# mainSchem.net
KiCad netlist of a schematic drawn in Altium Designer
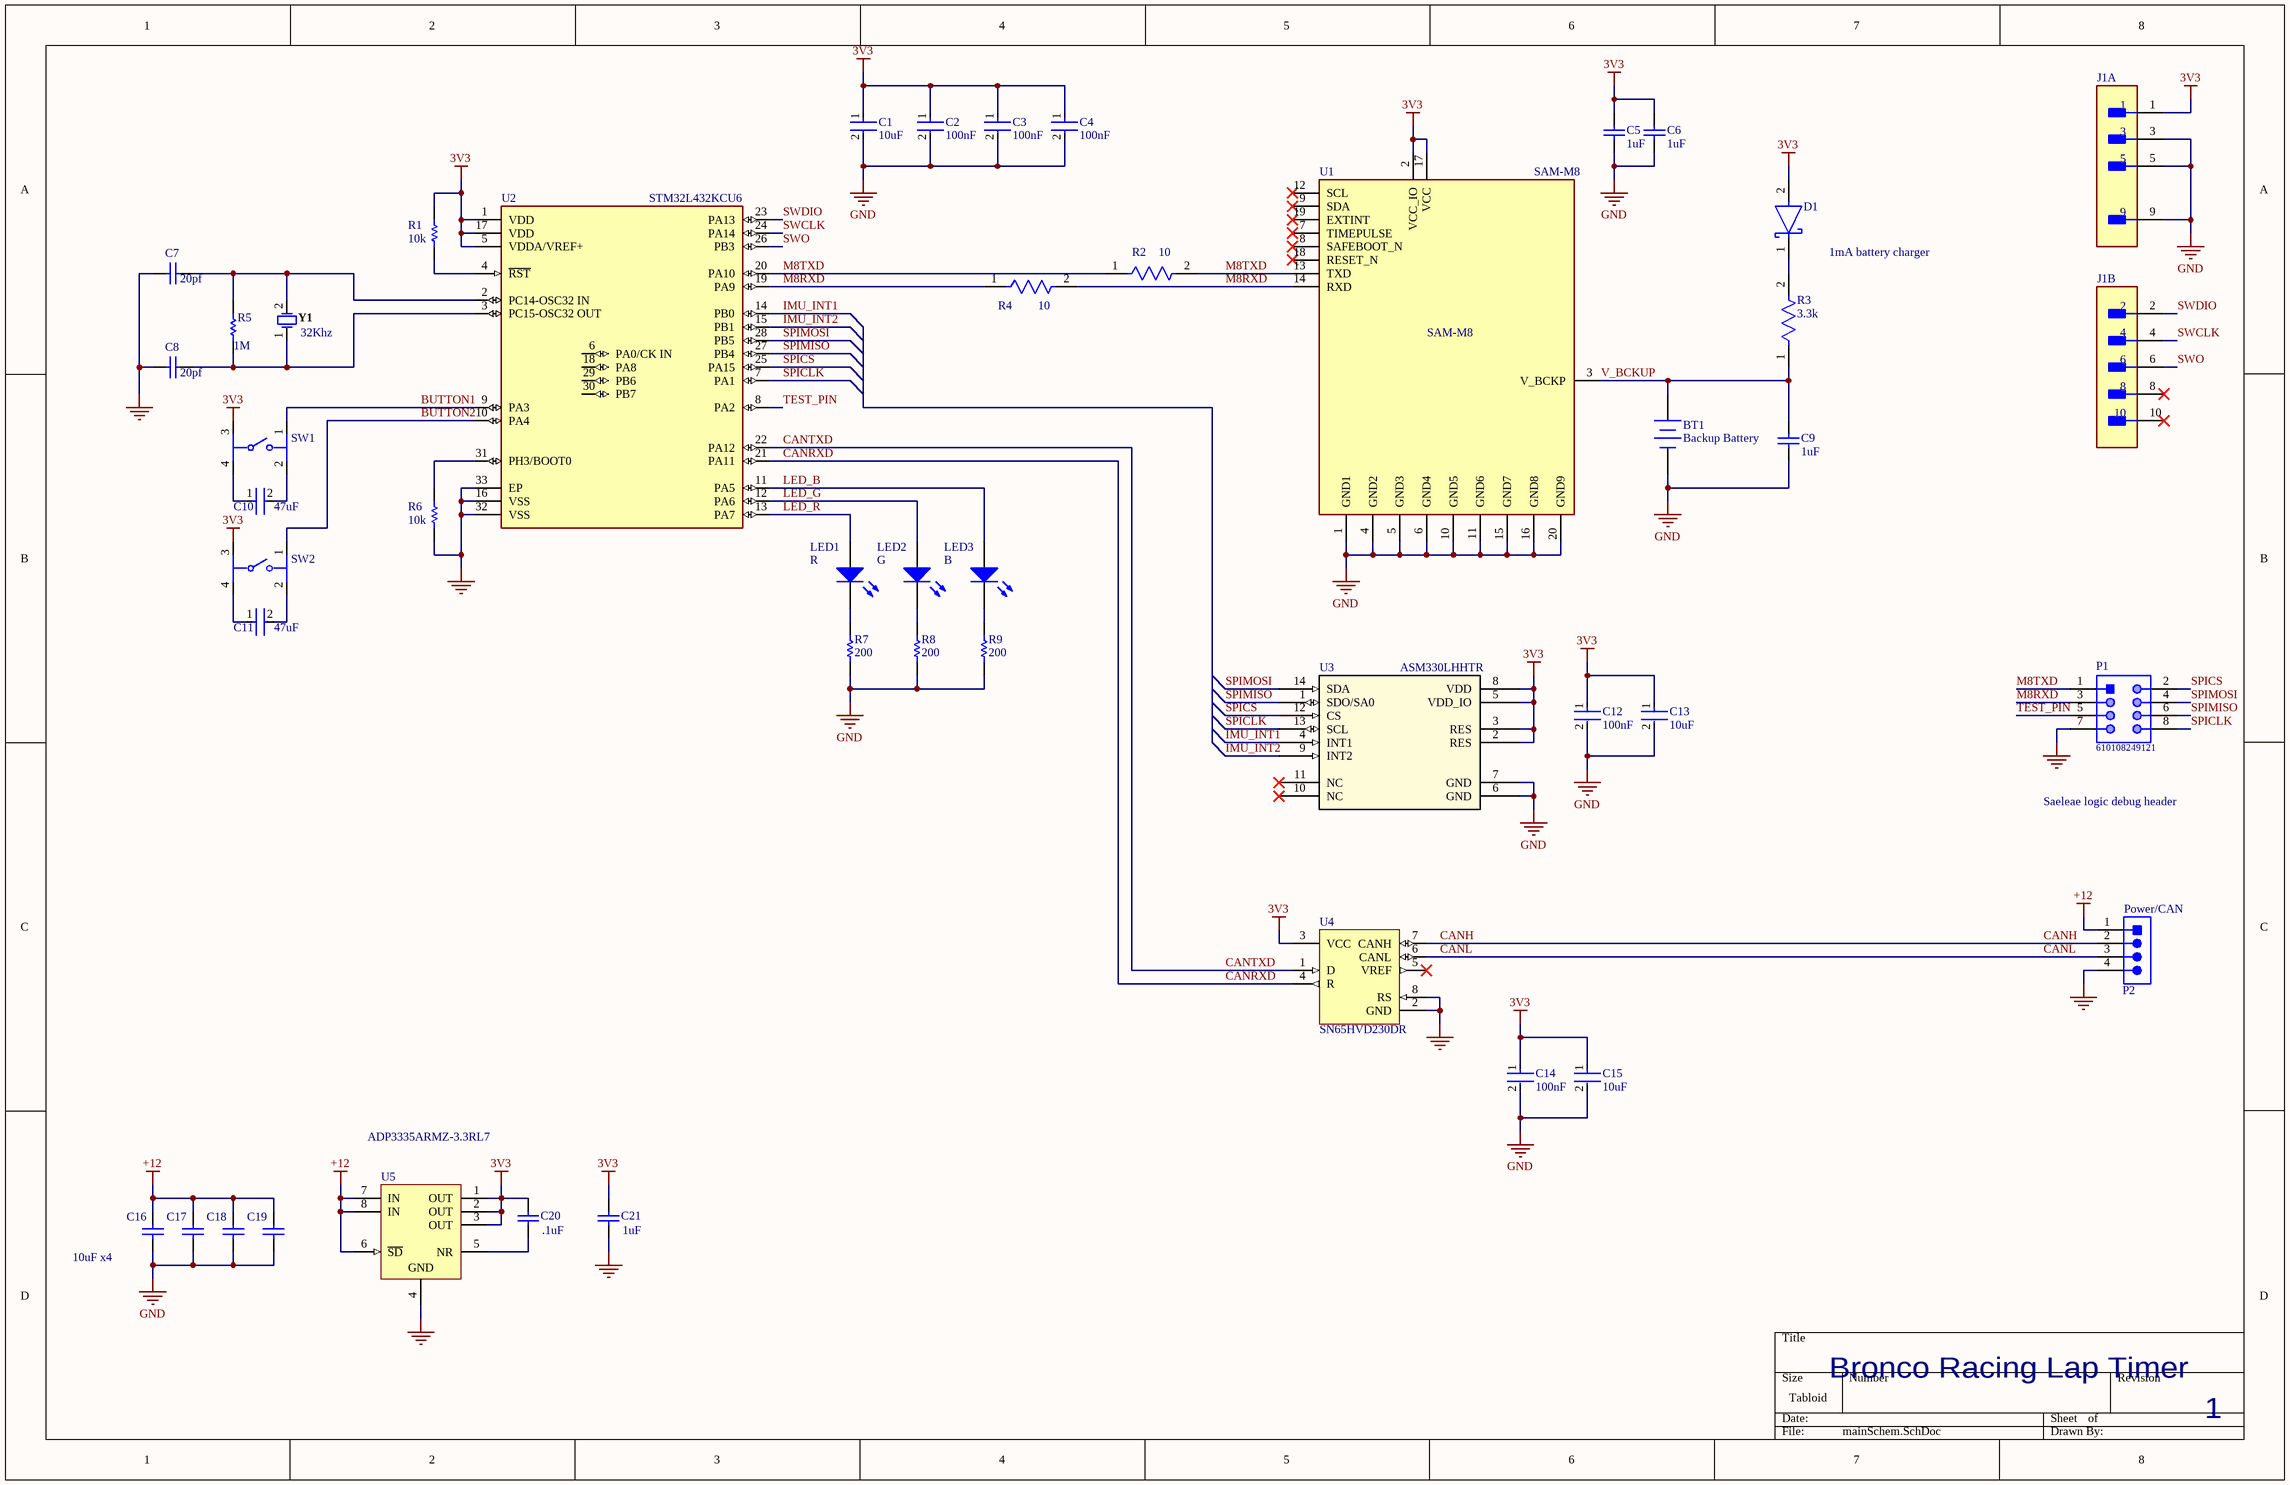
[diagram p0: mainSchem.SchDoc]

(export (version "E")
  (design (tool "Eeschema 10.0.6"))
  (components
    (comp (ref "BT1")
      (value "Backup Battery")
      (footprint "SEIK-MS621FE-FL11E-2_V")
      (description "MS Lihium Rechargeable Battery, 3 V, -20 to 60 degC, Tray")
      (fields (field (name "MANUFACTURER") "SeikoInstruments"))
      (libsource (lib "Altium Content Vault") (part "BATTERY_SINGLE-2"))
    )
    (comp (ref "C1")
      (value "10uF")
      (footprint "FP-C1608-080-MFG")
      (description "CAP CER 10UF 10V X5R 0603")
      (fields
        (field (name "MANUFACTURER PART NUMBER") "C1608X5R1A106K080AC")
        (field (name "OCTOPART") "https://octopart.com/c1608x5r1a106k080ac-tdk-26013468")
      )
      (libsource (lib "Altium Content Vault") (part "11868f565c42a9108669ba33697ecf6"))
    )
    (comp (ref "C2")
      (value "100nF")
      (footprint "FP-CGA3E-0_3-0_1-IPC_A")
      (description "Cap Ceramic 100nF 50V X7R 10% Pad SMD 0603 +125°C Automotive T/R")
      (fields (field (name "TOLERANCE") "10%") (field (name "VOLTAGE") "50V"))
      (libsource (lib "Altium Content Vault") (part "b4654b650e69147ec39a6b967a45e02"))
    )
    (comp (ref "C3")
      (value "100nF")
      (footprint "FP-CGA3E-0_3-0_1-IPC_A")
      (description "Cap Ceramic 100nF 50V X7R 10% Pad SMD 0603 +125°C Automotive T/R")
      (fields (field (name "TOLERANCE") "10%") (field (name "VOLTAGE") "50V"))
      (libsource (lib "Altium Content Vault") (part "b4654b650e69147ec39a6b967a45e02"))
    )
    (comp (ref "C4")
      (value "100nF")
      (footprint "FP-CGA3E-0_3-0_1-IPC_A")
      (description "Cap Ceramic 100nF 50V X7R 10% Pad SMD 0603 +125°C Automotive T/R")
      (fields (field (name "TOLERANCE") "10%") (field (name "VOLTAGE") "50V"))
      (libsource (lib "Altium Content Vault") (part "b4654b650e69147ec39a6b967a45e02"))
    )
    (comp (ref "C5")
      (value "1uF")
      (footprint "CAPC1608X90X35LL15T15")
      (fields (field (name "MANUFACTURER") "Kemet") (field (name "PART NUMBER") "C0603C105K3PAC7867"))
      (libsource (lib "Altium Content Vault") (part "CAP"))
    )
    (comp (ref "C6")
      (value "1uF")
      (footprint "CAPC1608X90X35LL15T15")
      (fields (field (name "MANUFACTURER") "Kemet") (field (name "PART NUMBER") "C0603C105K3PAC7867"))
      (libsource (lib "Altium Content Vault") (part "CAP"))
    )
    (comp (ref "C7")
      (value "08051A200JAT2A")
      (footprint "CAPC2013X140X50NL20T25")
      (fields (field (name "MANUFACTURER") "AVX Interconnect / Elco"))
      (libsource (lib "Altium Content Vault") (part "CAP"))
    )
    (comp (ref "C8")
      (value "08051A200JAT2A")
      (footprint "CAPC2013X140X50NL20T25")
      (fields (field (name "MANUFACTURER") "AVX Interconnect / Elco"))
      (libsource (lib "Altium Content Vault") (part "CAP"))
    )
    (comp (ref "C9")
      (value "1uF")
      (footprint "CAPC1608X90X35LL15T15")
      (fields (field (name "MANUFACTURER") "Kemet") (field (name "PART NUMBER") "C0603C105K3PAC7867"))
      (libsource (lib "Altium Content Vault") (part "CAP"))
    )
    (comp (ref "C10")
      (value "47uF")
      (footprint "FP-GRM188-0_2-IPC_B")
      (description "Chip Multilayer Ceramic Capacitors for General Purpose, 0603, 47uF, X5R, 15%, 20%, 6.3V")
      (fields (field (name "TOLERANCE") "20%"))
      (libsource (lib "Altium Content Vault") (part "11868f565c42a9108669ba33697ecf6"))
    )
    (comp (ref "C11")
      (value "47uF")
      (footprint "FP-GRM188-0_2-IPC_B")
      (description "Chip Multilayer Ceramic Capacitors for General Purpose, 0603, 47uF, X5R, 15%, 20%, 6.3V")
      (fields (field (name "TOLERANCE") "20%"))
      (libsource (lib "Altium Content Vault") (part "11868f565c42a9108669ba33697ecf6"))
    )
    (comp (ref "C12")
      (value "100nF")
      (footprint "FP-CGA3E-0_3-0_1-IPC_A")
      (description "Cap Ceramic 100nF 50V X7R 10% Pad SMD 0603 +125°C Automotive T/R")
      (fields (field (name "TOLERANCE") "10%") (field (name "VOLTAGE") "50V"))
      (libsource (lib "Altium Content Vault") (part "b4654b650e69147ec39a6b967a45e02"))
    )
    (comp (ref "C13")
      (value "10uF")
      (footprint "FP-C1608-080-MFG")
      (description "CAP CER 10UF 10V X5R 0603")
      (fields
        (field (name "MANUFACTURER PART NUMBER") "C1608X5R1A106K080AC")
        (field (name "OCTOPART") "https://octopart.com/c1608x5r1a106k080ac-tdk-26013468")
      )
      (libsource (lib "Altium Content Vault") (part "11868f565c42a9108669ba33697ecf6"))
    )
    (comp (ref "C14")
      (value "100nF")
      (footprint "FP-CGA3E-0_3-0_1-IPC_A")
      (description "Cap Ceramic 100nF 50V X7R 10% Pad SMD 0603 +125°C Automotive T/R")
      (fields (field (name "TOLERANCE") "10%") (field (name "VOLTAGE") "50V"))
      (libsource (lib "Altium Content Vault") (part "b4654b650e69147ec39a6b967a45e02"))
    )
    (comp (ref "C15")
      (value "10uF")
      (footprint "FP-C1608-080-MFG")
      (description "CAP CER 10UF 10V X5R 0603")
      (fields
        (field (name "MANUFACTURER PART NUMBER") "C1608X5R1A106K080AC")
        (field (name "OCTOPART") "https://octopart.com/c1608x5r1a106k080ac-tdk-26013468")
      )
      (libsource (lib "Altium Content Vault") (part "11868f565c42a9108669ba33697ecf6"))
    )
    (comp (ref "C16")
      (value "CGA5L3X5R1H106K160AB")
      (footprint "CAPC3216X190X20LL20")
      (description "Chip Capacitor, 10 uF, +/- 10%, 50 V, -55 to 85 degC, 1206 (3216 Metric), RoHS, Tape and Reel")
      (fields (field (name "MANUFACTURER") "TDK") (field (name "TOLERANCE") "10%"))
      (libsource (lib "Altium Content Vault") (part "CAP-NP-2"))
    )
    (comp (ref "C17")
      (value "CGA5L3X5R1H106K160AB")
      (footprint "CAPC3216X190X20LL20")
      (description "Chip Capacitor, 10 uF, +/- 10%, 50 V, -55 to 85 degC, 1206 (3216 Metric), RoHS, Tape and Reel")
      (fields (field (name "MANUFACTURER") "TDK") (field (name "TOLERANCE") "10%"))
      (libsource (lib "Altium Content Vault") (part "CAP-NP-2"))
    )
    (comp (ref "C18")
      (value "CGA5L3X5R1H106K160AB")
      (footprint "CAPC3216X190X20LL20")
      (description "Chip Capacitor, 10 uF, +/- 10%, 50 V, -55 to 85 degC, 1206 (3216 Metric), RoHS, Tape and Reel")
      (fields (field (name "MANUFACTURER") "TDK") (field (name "TOLERANCE") "10%"))
      (libsource (lib "Altium Content Vault") (part "CAP-NP-2"))
    )
    (comp (ref "C19")
      (value "CGA5L3X5R1H106K160AB")
      (footprint "CAPC3216X190X20LL20")
      (description "Chip Capacitor, 10 uF, +/- 10%, 50 V, -55 to 85 degC, 1206 (3216 Metric), RoHS, Tape and Reel")
      (fields (field (name "MANUFACTURER") "TDK") (field (name "TOLERANCE") "10%"))
      (libsource (lib "Altium Content Vault") (part "CAP-NP-2"))
    )
    (comp (ref "C20")
      (value "CGA3E2X7R1H104K080AA")
      (footprint "CAPC1608X90X20LL10")
      (description "Chip Capacitor, 0.1 uF, +/- 10%, 50 V, -55 to 125 degC, 0603 (1608 Metric), RoHS, Tape and Reel")
      (fields (field (name "VOLTAGE") "50V") (field (name "TOLERANCE") "10%"))
      (libsource (lib "Altium Content Vault") (part "CAP-NP-2"))
    )
    (comp (ref "C21")
      (value "GRM31MR71H105KA88L")
      (footprint "CAPC3216X125X55LL15T25")
      (description "Chip Capacitor, 1 uF, +/- 10%, 50 V, -55 to 125 degC, 1206 (3216 Metric), RoHS, Tape and Reel")
      (fields (field (name "TOLERANCE") "10%") (field (name "MANUFACTURER") "Murata"))
      (libsource (lib "Altium Content Vault") (part "CAP-NP-2"))
    )
    (comp (ref "D1")
      (value "SD0603S040S0R2")
      (footprint "FP-SD0603-MFG")
      (description "DIODE SCHOTTKY 40V 200MA 0603")
      (fields
        (field (name "MANUFACTURER") "AVX")
        (field (name "OCTOPART") "https://octopart.com/sd0603s040s0r2-avx-24931763")
      )
      (libsource (lib "Altium Content Vault") (part "1d6ec82d83fb6aee721767c19dac4b9"))
    )
    (comp (ref "J1")
      (value "FTSH-105-01-L-DV-007-K")
      (footprint "FP-FTSH-105-01-L-DV-007-K-MFG")
      (description "CONN HEADER SMD 10POS 1.27MM")
      (fields
        (field (name "OCTOPART") "https://octopart.com/ftsh-105-01-l-dv-007-k-samtec-53647300")
        (field (name "MANUFACTURER") "Samtec")
      )
      (libsource (lib "Altium Content Vault") (part "7c368be3265735b2816d0cab4417f87"))
    )
    (comp (ref "LED1")
      (value "150120RS75000")
      (footprint "1206_A")
      (description "SMD mono-color Chip LED, WL-SMCW, Red")
      (fields (field (name "MANUFACTURER") "Wuerth Elektronik"))
      (libsource (lib "Altium Content Vault") (part "WE-LED_K1A2-2"))
    )
    (comp (ref "LED2")
      (value "150120GS75000")
      (footprint "1206_A")
      (description "SMD mono-color Chip LED, WL-SMCW, Green")
      (fields (field (name "MANUFACTURER") "Wuerth Elektronik"))
      (libsource (lib "Altium Content Vault") (part "WE-LED_K1A2-2"))
    )
    (comp (ref "LED3")
      (value "150120BS75000")
      (footprint "1206_A")
      (description "SMD mono-color Chip LED, WL-SMCW, Blue")
      (fields (field (name "MANUFACTURER") "Wuerth Elektronik"))
      (libsource (lib "Altium Content Vault") (part "WE-LED_K1A2-2"))
    )
    (comp (ref "P1")
      (value "610108249121")
      (footprint "610108249121")
      (description "SMT Angled Pin Header WR-PHD, Pitch 2.54 mm, Dual Row, 8 pins")
      (fields (field (name "MANUFACTURER") "Wurth Elektronik") (field (name "PUBLISHER") "WurthElektronik"))
      (libsource (lib "Altium Content Vault") (part "WE-CN-2P-M-R8"))
    )
    (comp (ref "P2")
      (value "B4B-PH-K-S(LF)(SN)")
      (footprint "JST-B4B-PH-K-S_V")
      (fields (field (name "MANUFACTURER") "JST"))
      (libsource (lib "Altium Content Vault") (part "CN-1P-M-R4"))
    )
    (comp (ref "R1")
      (value "10k")
      (footprint "RESC1609X55X30LL15T15")
      (description "Chip Resistor, 10 KOhm, +/- 1%, 0.1 W, -55 to 155 degC, 0603 (1608 Metric), RoHS, Tape and Reel")
      (fields (field (name "TOLERANCE") "1%") (field (name "MANUFACTURER") "Panasonic"))
      (libsource (lib "Altium Content Vault") (part "RES-2"))
    )
    (comp (ref "R2")
      (value "10")
      (footprint "FP-RT0603-MFG")
      (description "RES SMD 10 OHM 0.1% 1/10W 0603")
      (fields (field (name "TOLERANCE") "0.001") (field (name "MANUFACTURER") "Yageo"))
      (libsource (lib "Altium Content Vault") (part "1029c3af85768c4190bb7ad29bc67b5"))
    )
    (comp (ref "R3")
      (value "3.3k")
      (footprint "FP-RT0603-MFG")
      (description "RES 3.30K OHM 1/10W 1% SMD 0603")
      (fields
        (field (name "OCTOPART") "https://octopart.com/rt0603fre073k3l-yageo-39814754")
        (field (name "MANUFACTURER PART NUMBER") "RT0603FRE073K3L")
      )
      (libsource (lib "Altium Content Vault") (part "1029c3af85768c4190bb7ad29bc67b5"))
    )
    (comp (ref "R4")
      (value "10")
      (footprint "FP-RT0603-MFG")
      (description "RES SMD 10 OHM 0.1% 1/10W 0603")
      (fields (field (name "TOLERANCE") "0.001") (field (name "MANUFACTURER") "Yageo"))
      (libsource (lib "Altium Content Vault") (part "1029c3af85768c4190bb7ad29bc67b5"))
    )
    (comp (ref "R5")
      (value "ERJ-8ENF1004V")
      (footprint "RESC3216X70X50NL05T20")
      (fields (field (name "MANUFACTURER") "Panasonic"))
      (libsource (lib "Altium Content Vault") (part "RES"))
    )
    (comp (ref "R6")
      (value "10k")
      (footprint "RESC1609X55X30LL15T15")
      (description "Chip Resistor, 10 KOhm, +/- 1%, 0.1 W, -55 to 155 degC, 0603 (1608 Metric), RoHS, Tape and Reel")
      (fields (field (name "TOLERANCE") "1%") (field (name "MANUFACTURER") "Panasonic"))
      (libsource (lib "Altium Content Vault") (part "RES-2"))
    )
    (comp (ref "R7")
      (value "200")
      (footprint "RESC1609X55X30NL10T20")
      (fields (field (name "PART NUMBER") "TNPW0603200RBEEA") (field (name "MANUFACTURER") "Vishay Dale"))
      (libsource (lib "Altium Content Vault") (part "RES"))
    )
    (comp (ref "R8")
      (value "200")
      (footprint "RESC1609X55X30NL10T20")
      (fields (field (name "PART NUMBER") "TNPW0603200RBEEA") (field (name "MANUFACTURER") "Vishay Dale"))
      (libsource (lib "Altium Content Vault") (part "RES"))
    )
    (comp (ref "R9")
      (value "200")
      (footprint "RESC1609X55X30NL10T20")
      (fields (field (name "PART NUMBER") "TNPW0603200RBEEA") (field (name "MANUFACTURER") "Vishay Dale"))
      (libsource (lib "Altium Content Vault") (part "RES"))
    )
    (comp (ref "SW1")
      (value "PTS645SM43SMTR92LFS")
      (footprint "FP-PTS645SM43SMTR92LFS-MFG")
      (description "SWITCH TACTILE SPST-NO 0.05A 12V")
      (libsource (lib "Altium Content Vault") (part "1adf0dd01260c80cf25a44bfd6b99ba"))
    )
    (comp (ref "SW2")
      (value "PTS645SM43SMTR92LFS")
      (footprint "FP-PTS645SM43SMTR92LFS-MFG")
      (description "SWITCH TACTILE SPST-NO 0.05A 12V")
      (libsource (lib "Altium Content Vault") (part "1adf0dd01260c80cf25a44bfd6b99ba"))
    )
    (comp (ref "U1")
      (value "SAM-M8")
      (footprint "SAM-M8")
      (description "u-blox SAM GNSS antenna module")
      (fields (field (name "MANUFACTURER") "u-blox"))
      (libsource (lib "ubloxLib") (part "SAM-M8"))
    )
    (comp (ref "U2")
      (value "STM32L432KCU6")
      (footprint "FP-UFQFPN32-A0B8-MFG")
      (description "IC MCU 32BIT 256KB FLASH 32QFPN")
      (fields
        (field (name "OCTOPART") "https://octopart.com/stm32l432kcu6-stmicroelectronics-71093510")
        (field (name "MANUFACTURER") "STMicroelectronics")
      )
      (libsource (lib "Altium Content Vault") (part "f3240dca552e0aa49c1b4baba198c12"))
    )
    (comp (ref "U3")
      (value "ASM330LHHTR")
      (footprint "LGA-14L_2P5X3X0P83_STM")
      (description "No Description Available")
      (fields (field (name "COPYRIGHT") "Copyright (C) 2018 Accelerated Designs. All rights reserved"))
      (libsource (lib "2021-01-05_19-36-17") (part "ASM330LHHTR"))
    )
    (comp (ref "U4")
      (value "SN65HVD230DR")
      (footprint "D0008A_L")
      (fields (field (name "MANUFACTURER") "Texas Instruments"))
      (libsource (lib "Altium Content Vault") (part "TI-SN65HVD230-SOIC_D-8"))
    )
    (comp (ref "U5")
      (value "ADP3335ARMZ-3.3RL7")
      (footprint "ADI-RM-8_L")
      (fields (field (name "MANUFACTURER") "Analog Devices"))
      (libsource (lib "Altium Content Vault") (part "ADI-ADP3335-RM-8"))
    )
    (comp (ref "Y1")
      (value "ABS07-120-32.768KHZ-T")
      (footprint "ABRA-ABS07_A_V")
      (description "Tuning Fork Crystal, 32.768 KHz, +/- 20 ppm, -40 to 85 degC, 2-Pin SMD, RoHS, Tape and Reel")
      (fields (field (name "MANUFACTURER") "Abracon") (field (name "TOLERANCE") "20ppm"))
      (libsource (lib "Altium Content Vault") (part "XTAL-1-2-2"))
    )
  )
  (nets
    (net (code "1") (name "+12") (class "Default")
      (node (ref "C16") (pin "1") (pinfunction "1_1") (pintype "passive"))
      (node (ref "C17") (pin "1") (pinfunction "1_1") (pintype "passive"))
      (node (ref "C18") (pin "1") (pinfunction "1_1") (pintype "passive"))
      (node (ref "C19") (pin "1") (pinfunction "1_1") (pintype "passive"))
      (node (ref "P2") (pin "1") (pinfunction "1_1") (pintype "passive"))
      (node (ref "U5") (pin "6") (pinfunction "~{SD}_6") (pintype "input"))
      (node (ref "U5") (pin "7") (pinfunction "IN_7") (pintype "power_in"))
      (node (ref "U5") (pin "8") (pinfunction "IN_8") (pintype "power_in"))
    )
    (net (code "3") (name "/BUTTON1") (class "Default")
      (node (ref "SW1") (pin "1") (pinfunction "1_1") (pintype "passive"))
      (node (ref "U2") (pin "9") (pinfunction "PA3_9") (pintype "bidirectional"))
    )
    (net (code "4") (name "/BUTTON2") (class "Default")
      (node (ref "SW2") (pin "1") (pinfunction "1_1") (pintype "passive"))
      (node (ref "U2") (pin "10") (pinfunction "PA4_10") (pintype "bidirectional"))
    )
    (net (code "5") (name "/CANH") (class "Default")
      (node (ref "P2") (pin "2") (pinfunction "2_2") (pintype "passive"))
      (node (ref "U4") (pin "7") (pinfunction "CANH_7") (pintype "bidirectional"))
    )
    (net (code "6") (name "/CANL") (class "Default")
      (node (ref "P2") (pin "3") (pinfunction "3_3") (pintype "passive"))
      (node (ref "U4") (pin "6") (pinfunction "CANL_6") (pintype "bidirectional"))
    )
    (net (code "7") (name "/CANRXD") (class "Default")
      (node (ref "U2") (pin "21") (pinfunction "PA11_21") (pintype "bidirectional"))
      (node (ref "U4") (pin "4") (pinfunction "R_4") (pintype "output"))
    )
    (net (code "8") (name "/CANTXD") (class "Default")
      (node (ref "U2") (pin "22") (pinfunction "PA12_22") (pintype "bidirectional"))
      (node (ref "U4") (pin "1") (pinfunction "D_1") (pintype "input"))
    )
    (net (code "9") (name "/IMU_INT1") (class "Default")
      (node (ref "U2") (pin "14") (pinfunction "PB0_14") (pintype "bidirectional"))
      (node (ref "U3") (pin "4") (pinfunction "INT1_4") (pintype "input"))
    )
    (net (code "10") (name "/IMU_INT2") (class "Default")
      (node (ref "U2") (pin "15") (pinfunction "PB1_15") (pintype "bidirectional"))
      (node (ref "U3") (pin "9") (pinfunction "INT2_9") (pintype "input"))
    )
    (net (code "11") (name "/LED_B") (class "Default")
      (node (ref "LED3") (pin "2") (pinfunction "A_2") (pintype "passive"))
      (node (ref "U2") (pin "11") (pinfunction "PA5_11") (pintype "bidirectional"))
    )
    (net (code "12") (name "/LED_G") (class "Default")
      (node (ref "LED2") (pin "2") (pinfunction "A_2") (pintype "passive"))
      (node (ref "U2") (pin "12") (pinfunction "PA6_12") (pintype "bidirectional"))
    )
    (net (code "13") (name "/LED_R") (class "Default")
      (node (ref "LED1") (pin "2") (pinfunction "A_2") (pintype "passive"))
      (node (ref "U2") (pin "13") (pinfunction "PA7_13") (pintype "bidirectional"))
    )
    (net (code "14") (name "/M8RXD") (class "Default")
      (node (ref "P1") (pin "3") (pinfunction "3_3") (pintype "passive"))
      (node (ref "R4") (pin "1") (pinfunction "1_1") (pintype "passive"))
      (node (ref "R4") (pin "2") (pinfunction "2_2") (pintype "passive"))
      (node (ref "U1") (pin "14") (pinfunction "RXD_14") (pintype "passive"))
      (node (ref "U2") (pin "19") (pinfunction "PA9_19") (pintype "bidirectional"))
    )
    (net (code "15") (name "/M8TXD") (class "Default")
      (node (ref "P1") (pin "1") (pinfunction "1_1") (pintype "passive"))
      (node (ref "R2") (pin "1") (pinfunction "1_1") (pintype "passive"))
      (node (ref "R2") (pin "2") (pinfunction "2_2") (pintype "passive"))
      (node (ref "U1") (pin "13") (pinfunction "TXD_13") (pintype "passive"))
      (node (ref "U2") (pin "20") (pinfunction "PA10_20") (pintype "bidirectional"))
    )
    (net (code "16") (name "/SPICLK") (class "Default")
      (node (ref "P1") (pin "8") (pinfunction "8_8") (pintype "passive"))
      (node (ref "U2") (pin "7") (pinfunction "PA1_7") (pintype "bidirectional"))
      (node (ref "U3") (pin "13") (pinfunction "SCL_13") (pintype "bidirectional"))
    )
    (net (code "17") (name "/SPICS") (class "Default")
      (node (ref "P1") (pin "2") (pinfunction "2_2") (pintype "passive"))
      (node (ref "U2") (pin "25") (pinfunction "PA15_25") (pintype "bidirectional"))
      (node (ref "U3") (pin "12") (pinfunction "CS_12") (pintype "input"))
    )
    (net (code "18") (name "/SPIMISO") (class "Default")
      (node (ref "P1") (pin "6") (pinfunction "6_6") (pintype "passive"))
      (node (ref "U2") (pin "27") (pinfunction "PB4_27") (pintype "bidirectional"))
      (node (ref "U3") (pin "1") (pinfunction "SDO/SA0_1") (pintype "bidirectional"))
    )
    (net (code "19") (name "/SPIMOSI") (class "Default")
      (node (ref "P1") (pin "4") (pinfunction "4_4") (pintype "passive"))
      (node (ref "U2") (pin "28") (pinfunction "PB5_28") (pintype "bidirectional"))
      (node (ref "U3") (pin "14") (pinfunction "SDA_14") (pintype "input"))
    )
    (net (code "20") (name "/SWCLK") (class "Default")
      (node (ref "J1") (pin "4") (pinfunction "4_4") (pintype "passive"))
      (node (ref "U2") (pin "24") (pinfunction "PA14_24") (pintype "bidirectional"))
    )
    (net (code "21") (name "/SWDIO") (class "Default")
      (node (ref "J1") (pin "2") (pinfunction "2_2") (pintype "passive"))
      (node (ref "U2") (pin "23") (pinfunction "PA13_23") (pintype "bidirectional"))
    )
    (net (code "22") (name "/SWO") (class "Default")
      (node (ref "J1") (pin "6") (pinfunction "6_6") (pintype "passive"))
      (node (ref "U2") (pin "26") (pinfunction "PB3_26") (pintype "bidirectional"))
    )
    (net (code "23") (name "/TEST_PIN") (class "Default")
      (node (ref "P1") (pin "5") (pinfunction "5_5") (pintype "passive"))
      (node (ref "U2") (pin "8") (pinfunction "PA2_8") (pintype "bidirectional"))
    )
    (net (code "24") (name "/V_BCKUP") (class "Default")
      (node (ref "BT1") (pin "1") (pinfunction "+_1") (pintype "passive"))
      (node (ref "C9") (pin "2") (pinfunction "2_2") (pintype "passive"))
      (node (ref "R3") (pin "1") (pinfunction "1_1") (pintype "passive"))
      (node (ref "U1") (pin "3") (pinfunction "V_BCKP_3") (pintype "passive"))
    )
    (net (code "25") (name "3V3") (class "Default")
      (node (ref "C1") (pin "1") (pinfunction "1_1") (pintype "passive"))
      (node (ref "C12") (pin "1") (pinfunction "1_1") (pintype "passive"))
      (node (ref "C13") (pin "1") (pinfunction "1_1") (pintype "passive"))
      (node (ref "C14") (pin "1") (pinfunction "1_1") (pintype "passive"))
      (node (ref "C15") (pin "1") (pinfunction "1_1") (pintype "passive"))
      (node (ref "C2") (pin "1") (pinfunction "1_1") (pintype "passive"))
      (node (ref "C20") (pin "1") (pinfunction "1_1") (pintype "passive"))
      (node (ref "C21") (pin "1") (pinfunction "1_1") (pintype "passive"))
      (node (ref "C3") (pin "1") (pinfunction "1_1") (pintype "passive"))
      (node (ref "C4") (pin "1") (pinfunction "1_1") (pintype "passive"))
      (node (ref "C5") (pin "2") (pinfunction "2_2") (pintype "passive"))
      (node (ref "C6") (pin "2") (pinfunction "2_2") (pintype "passive"))
      (node (ref "D1") (pin "2") (pinfunction "A_2") (pintype "passive"))
      (node (ref "J1") (pin "1") (pinfunction "1_1") (pintype "passive"))
      (node (ref "R1") (pin "1") (pinfunction "1_1") (pintype "passive"))
      (node (ref "SW1") (pin "3") (pinfunction "3_3") (pintype "passive"))
      (node (ref "SW2") (pin "3") (pinfunction "3_3") (pintype "passive"))
      (node (ref "U1") (pin "17") (pinfunction "VCC_17") (pintype "passive"))
      (node (ref "U1") (pin "2") (pinfunction "VCC_IO_2") (pintype "passive"))
      (node (ref "U2") (pin "1") (pinfunction "VDD_1") (pintype "power_in"))
      (node (ref "U2") (pin "17") (pinfunction "VDD_17") (pintype "power_in"))
      (node (ref "U2") (pin "5") (pinfunction "VDDA/VREF+_5") (pintype "power_in"))
      (node (ref "U3") (pin "2") (pinfunction "RES_2") (pintype "passive"))
      (node (ref "U3") (pin "3") (pinfunction "RES_3") (pintype "passive"))
      (node (ref "U3") (pin "5") (pinfunction "VDD_IO_5") (pintype "power_in"))
      (node (ref "U3") (pin "8") (pinfunction "VDD_8") (pintype "power_in"))
      (node (ref "U4") (pin "3") (pinfunction "VCC_3") (pintype "power_in"))
      (node (ref "U5") (pin "1") (pinfunction "OUT_1") (pintype "power_in"))
      (node (ref "U5") (pin "2") (pinfunction "OUT_2") (pintype "power_in"))
      (node (ref "U5") (pin "3") (pinfunction "OUT_3") (pintype "power_in"))
    )
    (net (code "26") (name "GND") (class "Default")
      (node (ref "BT1") (pin "2") (pinfunction "-_2") (pintype "passive"))
      (node (ref "C1") (pin "2") (pinfunction "2_2") (pintype "passive"))
      (node (ref "C12") (pin "2") (pinfunction "2_2") (pintype "passive"))
      (node (ref "C13") (pin "2") (pinfunction "2_2") (pintype "passive"))
      (node (ref "C14") (pin "2") (pinfunction "2_2") (pintype "passive"))
      (node (ref "C15") (pin "2") (pinfunction "2_2") (pintype "passive"))
      (node (ref "C16") (pin "2") (pinfunction "2_2") (pintype "passive"))
      (node (ref "C17") (pin "2") (pinfunction "2_2") (pintype "passive"))
      (node (ref "C18") (pin "2") (pinfunction "2_2") (pintype "passive"))
      (node (ref "C19") (pin "2") (pinfunction "2_2") (pintype "passive"))
      (node (ref "C2") (pin "2") (pinfunction "2_2") (pintype "passive"))
      (node (ref "C21") (pin "2") (pinfunction "2_2") (pintype "passive"))
      (node (ref "C3") (pin "2") (pinfunction "2_2") (pintype "passive"))
      (node (ref "C4") (pin "2") (pinfunction "2_2") (pintype "passive"))
      (node (ref "C5") (pin "1") (pinfunction "1_1") (pintype "passive"))
      (node (ref "C6") (pin "1") (pinfunction "1_1") (pintype "passive"))
      (node (ref "C7") (pin "1") (pinfunction "1_1") (pintype "passive"))
      (node (ref "C8") (pin "1") (pinfunction "1_1") (pintype "passive"))
      (node (ref "C9") (pin "1") (pinfunction "1_1") (pintype "passive"))
      (node (ref "J1") (pin "3") (pinfunction "3_3") (pintype "passive"))
      (node (ref "J1") (pin "5") (pinfunction "5_5") (pintype "passive"))
      (node (ref "J1") (pin "9") (pinfunction "9_9") (pintype "passive"))
      (node (ref "P1") (pin "7") (pinfunction "7_7") (pintype "passive"))
      (node (ref "P2") (pin "4") (pinfunction "4_4") (pintype "passive"))
      (node (ref "R6") (pin "2") (pinfunction "2_2") (pintype "passive"))
      (node (ref "R7") (pin "1") (pinfunction "1_1") (pintype "passive"))
      (node (ref "R8") (pin "1") (pinfunction "1_1") (pintype "passive"))
      (node (ref "R9") (pin "1") (pinfunction "1_1") (pintype "passive"))
      (node (ref "U1") (pin "1") (pinfunction "GND1_1") (pintype "passive"))
      (node (ref "U1") (pin "10") (pinfunction "GND5_10") (pintype "passive"))
      (node (ref "U1") (pin "11") (pinfunction "GND6_11") (pintype "passive"))
      (node (ref "U1") (pin "15") (pinfunction "GND7_15") (pintype "passive"))
      (node (ref "U1") (pin "16") (pinfunction "GND8_16") (pintype "passive"))
      (node (ref "U1") (pin "20") (pinfunction "GND9_20") (pintype "passive"))
      (node (ref "U1") (pin "4") (pinfunction "GND2_4") (pintype "passive"))
      (node (ref "U1") (pin "5") (pinfunction "GND3_5") (pintype "passive"))
      (node (ref "U1") (pin "6") (pinfunction "GND4_6") (pintype "passive"))
      (node (ref "U2") (pin "16") (pinfunction "VSS_16") (pintype "power_in"))
      (node (ref "U2") (pin "32") (pinfunction "VSS_32") (pintype "power_in"))
      (node (ref "U2") (pin "33") (pinfunction "EP_33") (pintype "power_in"))
      (node (ref "U3") (pin "6") (pinfunction "GND_6") (pintype "passive"))
      (node (ref "U3") (pin "7") (pinfunction "GND_7") (pintype "passive"))
      (node (ref "U4") (pin "2") (pinfunction "GND_2") (pintype "power_in"))
      (node (ref "U4") (pin "8") (pinfunction "RS_8") (pintype "input"))
      (node (ref "U5") (pin "4") (pinfunction "GND_4") (pintype "power_in"))
    )
    (net (code "27") (name "Net-(C10-Pad1)") (class "Default")
      (node (ref "C10") (pin "1") (pinfunction "1_1") (pintype "passive"))
      (node (ref "SW1") (pin "4") (pinfunction "4_4") (pintype "passive"))
    )
    (net (code "28") (name "Net-(C10-Pad2)") (class "Default")
      (node (ref "C10") (pin "2") (pinfunction "2_2") (pintype "passive"))
      (node (ref "SW1") (pin "2") (pinfunction "2_2") (pintype "passive"))
    )
    (net (code "29") (name "Net-(C11-Pad1)") (class "Default")
      (node (ref "C11") (pin "1") (pinfunction "1_1") (pintype "passive"))
      (node (ref "SW2") (pin "4") (pinfunction "4_4") (pintype "passive"))
    )
    (net (code "30") (name "Net-(C11-Pad2)") (class "Default")
      (node (ref "C11") (pin "2") (pinfunction "2_2") (pintype "passive"))
      (node (ref "SW2") (pin "2") (pinfunction "2_2") (pintype "passive"))
    )
    (net (code "31") (name "Net-(D1-C)") (class "Default")
      (node (ref "D1") (pin "1") (pinfunction "C_1") (pintype "passive"))
      (node (ref "R3") (pin "2") (pinfunction "2_2") (pintype "passive"))
    )
    (net (code "32") (name "Net-(LED1-K)") (class "Default")
      (node (ref "LED1") (pin "1") (pinfunction "K_1") (pintype "passive"))
      (node (ref "R7") (pin "2") (pinfunction "2_2") (pintype "passive"))
    )
    (net (code "33") (name "Net-(LED2-K)") (class "Default")
      (node (ref "LED2") (pin "1") (pinfunction "K_1") (pintype "passive"))
      (node (ref "R8") (pin "2") (pinfunction "2_2") (pintype "passive"))
    )
    (net (code "34") (name "Net-(LED3-K)") (class "Default")
      (node (ref "LED3") (pin "1") (pinfunction "K_1") (pintype "passive"))
      (node (ref "R9") (pin "2") (pinfunction "2_2") (pintype "passive"))
    )
    (net (code "35") (name "Net-(U2-PC14-OSC32_IN)") (class "Default")
      (node (ref "C7") (pin "2") (pinfunction "2_2") (pintype "passive"))
      (node (ref "R5") (pin "1") (pinfunction "1_1") (pintype "passive"))
      (node (ref "U2") (pin "2") (pinfunction "PC14-OSC32_IN_2") (pintype "bidirectional"))
      (node (ref "Y1") (pin "2") (pinfunction "2_2") (pintype "passive"))
    )
    (net (code "36") (name "Net-(U2-PC15-OSC32_OUT)") (class "Default")
      (node (ref "C8") (pin "2") (pinfunction "2_2") (pintype "passive"))
      (node (ref "R5") (pin "2") (pinfunction "2_2") (pintype "passive"))
      (node (ref "U2") (pin "3") (pinfunction "PC15-OSC32_OUT_3") (pintype "bidirectional"))
      (node (ref "Y1") (pin "1") (pinfunction "1_1") (pintype "passive"))
    )
    (net (code "37") (name "Net-(U2-PH3{slash}BOOT0)") (class "Default")
      (node (ref "R6") (pin "1") (pinfunction "1_1") (pintype "passive"))
      (node (ref "U2") (pin "31") (pinfunction "PH3/BOOT0_31") (pintype "bidirectional"))
    )
    (net (code "38") (name "Net-(U2-~{RST})") (class "Default")
      (node (ref "R1") (pin "2") (pinfunction "2_2") (pintype "passive"))
      (node (ref "U2") (pin "4") (pinfunction "~{RST}_4") (pintype "input"))
    )
    (net (code "39") (name "Net-(U5-NR)") (class "Default")
      (node (ref "C20") (pin "2") (pinfunction "2_2") (pintype "passive"))
      (node (ref "U5") (pin "5") (pinfunction "NR_5") (pintype "passive"))
    )
    (net (code "40") (name "unconnected-(J1-Pad8)") (class "Default")
      (node (ref "J1") (pin "8") (pinfunction "8_8") (pintype "passive+no_connect"))
    )
    (net (code "41") (name "unconnected-(J1-Pad10)") (class "Default")
      (node (ref "J1") (pin "10") (pinfunction "10_10") (pintype "passive+no_connect"))
    )
    (net (code "42") (name "unconnected-(U1-EXTINT-Pad19)") (class "Default")
      (node (ref "U1") (pin "19") (pinfunction "EXTINT_19") (pintype "passive+no_connect"))
    )
    (net (code "43") (name "unconnected-(U1-RESET_N-Pad18)") (class "Default")
      (node (ref "U1") (pin "18") (pinfunction "RESET_N_18") (pintype "passive+no_connect"))
    )
    (net (code "44") (name "unconnected-(U1-SAFEBOOT_N-Pad8)") (class "Default")
      (node (ref "U1") (pin "8") (pinfunction "SAFEBOOT_N_8") (pintype "passive+no_connect"))
    )
    (net (code "45") (name "unconnected-(U1-SCL-Pad12)") (class "Default")
      (node (ref "U1") (pin "12") (pinfunction "SCL_12") (pintype "passive+no_connect"))
    )
    (net (code "46") (name "unconnected-(U1-SDA-Pad9)") (class "Default")
      (node (ref "U1") (pin "9") (pinfunction "SDA_9") (pintype "passive+no_connect"))
    )
    (net (code "47") (name "unconnected-(U1-TIMEPULSE-Pad7)") (class "Default")
      (node (ref "U1") (pin "7") (pinfunction "TIMEPULSE_7") (pintype "passive+no_connect"))
    )
    (net (code "48") (name "unconnected-(U2-PA0{slash}CK_IN-Pad6)") (class "Default")
      (node (ref "U2") (pin "6") (pinfunction "PA0/CK_IN_6") (pintype "bidirectional"))
    )
    (net (code "49") (name "unconnected-(U2-PA8-Pad18)") (class "Default")
      (node (ref "U2") (pin "18") (pinfunction "PA8_18") (pintype "bidirectional"))
    )
    (net (code "50") (name "unconnected-(U2-PB6-Pad29)") (class "Default")
      (node (ref "U2") (pin "29") (pinfunction "PB6_29") (pintype "bidirectional"))
    )
    (net (code "51") (name "unconnected-(U2-PB7-Pad30)") (class "Default")
      (node (ref "U2") (pin "30") (pinfunction "PB7_30") (pintype "bidirectional"))
    )
    (net (code "52") (name "unconnected-(U3-NC-Pad10)") (class "Default")
      (node (ref "U3") (pin "10") (pinfunction "NC_10") (pintype "passive+no_connect"))
    )
    (net (code "53") (name "unconnected-(U3-NC-Pad11)") (class "Default")
      (node (ref "U3") (pin "11") (pinfunction "NC_11") (pintype "passive+no_connect"))
    )
    (net (code "54") (name "unconnected-(U4-VREF-Pad5)") (class "Default")
      (node (ref "U4") (pin "5") (pinfunction "VREF_5") (pintype "output+no_connect"))
    )
  )
)
